# mic-preamp-stereo7.net
KiCad netlist of a schematic drawn in EAGLE
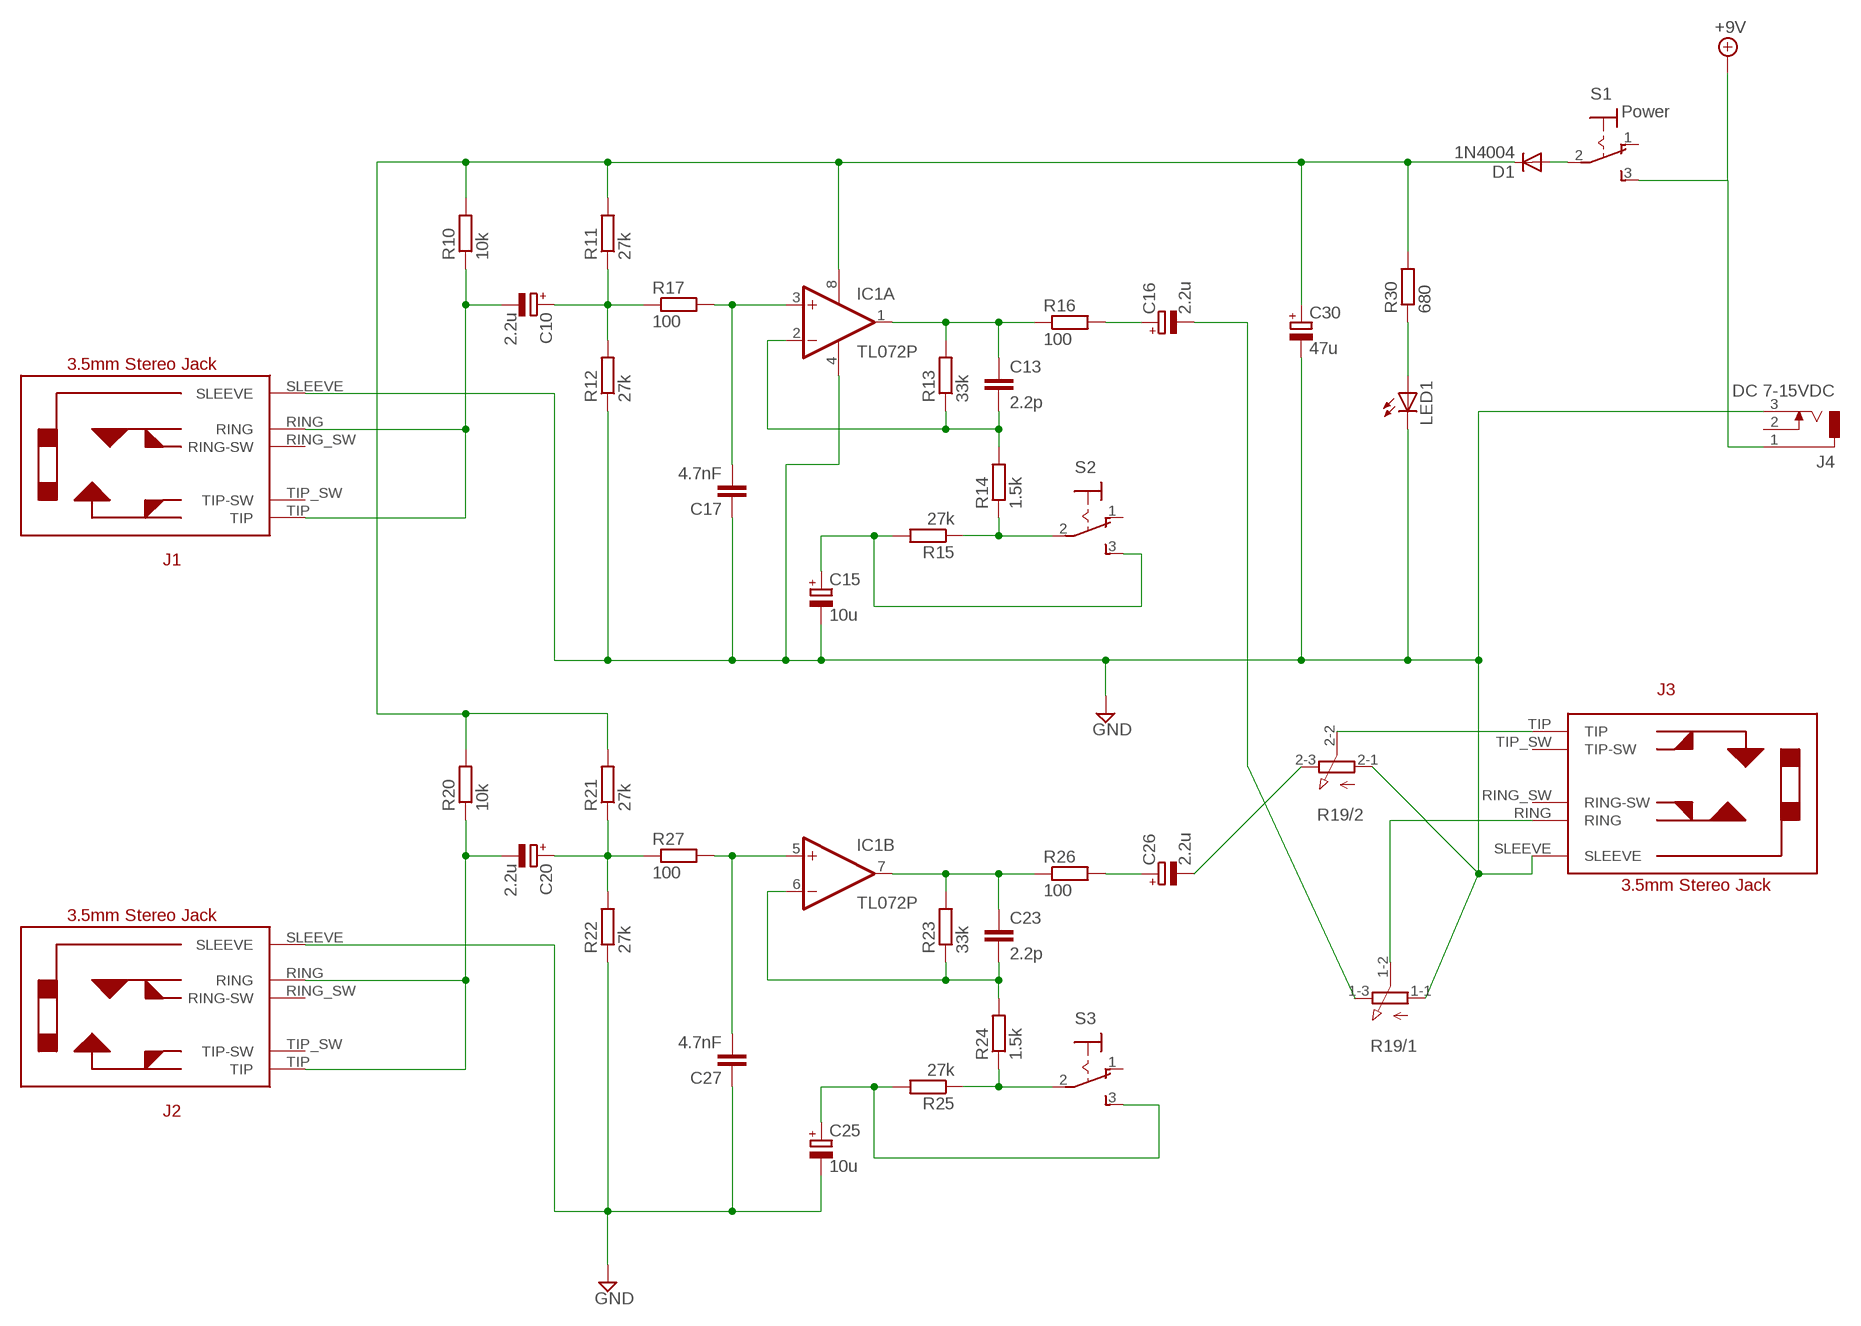
[diagram p0: schematic, sheet 1]

(export (version "E")
  (design (tool "Eeschema 10.0.6"))
  (components
    (comp (ref "C10")
      (value "2.2u")
      (footprint "eagle-import:E2-5")
      (libsource (lib "eagle-import") (part "CPOL-EUE2-5"))
    )
    (comp (ref "C13")
      (value "2.2p")
      (footprint "eagle-import:C025-024X044")
      (libsource (lib "eagle-import") (part "C-EU025-024X044"))
    )
    (comp (ref "C15")
      (value "10u")
      (footprint "eagle-import:E2-5")
      (libsource (lib "eagle-import") (part "CPOL-EUE2-5"))
    )
    (comp (ref "C16")
      (value "2.2u")
      (footprint "eagle-import:E2-5")
      (libsource (lib "eagle-import") (part "CPOL-EUE2-5"))
    )
    (comp (ref "C17")
      (value "4.7nF")
      (footprint "eagle-import:C025-024X044")
      (libsource (lib "eagle-import") (part "C-EU025-024X044"))
    )
    (comp (ref "C20")
      (value "2.2u")
      (footprint "eagle-import:E2-5")
      (libsource (lib "eagle-import") (part "CPOL-EUE2-5"))
    )
    (comp (ref "C23")
      (value "2.2p")
      (footprint "eagle-import:C025-024X044")
      (libsource (lib "eagle-import") (part "C-EU025-024X044"))
    )
    (comp (ref "C25")
      (value "10u")
      (footprint "eagle-import:E2-5")
      (libsource (lib "eagle-import") (part "CPOL-EUE2-5"))
    )
    (comp (ref "C26")
      (value "2.2u")
      (footprint "eagle-import:E2-5")
      (libsource (lib "eagle-import") (part "CPOL-EUE2-5"))
    )
    (comp (ref "C27")
      (value "4.7nF")
      (footprint "eagle-import:C025-024X044")
      (libsource (lib "eagle-import") (part "C-EU025-024X044"))
    )
    (comp (ref "C30")
      (value "47u")
      (footprint "eagle-import:E2-5")
      (libsource (lib "eagle-import") (part "CPOL-EUE2-5"))
    )
    (comp (ref "D1")
      (value "1N4004")
      (footprint "eagle-import:DO41-10")
      (libsource (lib "eagle-import") (part "1N4004"))
    )
    (comp (ref "IC1")
      (value "TL072P")
      (footprint "eagle-import:DIL08")
      (libsource (lib "eagle-import") (part "TL072P"))
    )
    (comp (ref "J1")
      (value "PICAXE_STEREOJACKSOCKET")
      (footprint "eagle-import:PICAXE_STEREOJACKSOCKET")
      (libsource (lib "eagle-import") (part "PICAXE_STEREOJACKSOCKET"))
    )
    (comp (ref "J2")
      (value "PICAXE_STEREOJACKSOCKET")
      (footprint "eagle-import:PICAXE_STEREOJACKSOCKET")
      (libsource (lib "eagle-import") (part "PICAXE_STEREOJACKSOCKET"))
    )
    (comp (ref "J3")
      (value "Stereo Out")
      (footprint "eagle-import:PICAXE_STEREOJACKSOCKET")
      (libsource (lib "eagle-import") (part "PICAXE_STEREOJACKSOCKET"))
    )
    (comp (ref "J4")
      (value "DC 7-15VDC")
      (footprint "eagle-import:DCJ0202")
      (libsource (lib "eagle-import") (part "DCJ0202"))
    )
    (comp (ref "LED1")
      (value "LED5MM")
      (footprint "eagle-import:LED5MM")
      (libsource (lib "eagle-import") (part "LED5MM"))
    )
    (comp (ref "R10")
      (value "10k")
      (footprint "eagle-import:0207_5V")
      (libsource (lib "eagle-import") (part "R-EU_0207/5V"))
    )
    (comp (ref "R11")
      (value "27k")
      (footprint "eagle-import:0207_5V")
      (libsource (lib "eagle-import") (part "R-EU_0207/5V"))
    )
    (comp (ref "R12")
      (value "27k")
      (footprint "eagle-import:0207_5V")
      (libsource (lib "eagle-import") (part "R-EU_0207/5V"))
    )
    (comp (ref "R13")
      (value "33k")
      (footprint "eagle-import:0207_5V")
      (libsource (lib "eagle-import") (part "R-EU_0207/5V"))
    )
    (comp (ref "R14")
      (value "1.5k")
      (footprint "eagle-import:0207_5V")
      (libsource (lib "eagle-import") (part "R-EU_0207/5V"))
    )
    (comp (ref "R15")
      (value "27k")
      (footprint "eagle-import:0207_5V")
      (libsource (lib "eagle-import") (part "R-EU_0207/5V"))
    )
    (comp (ref "R16")
      (value "100")
      (footprint "eagle-import:0207_5V")
      (libsource (lib "eagle-import") (part "R-EU_0207/5V"))
    )
    (comp (ref "R17")
      (value "100")
      (footprint "eagle-import:0207_5V")
      (libsource (lib "eagle-import") (part "resistor_R-EU_0207/5V"))
    )
    (comp (ref "R19")
      (value "3RP/1610G")
      (footprint "eagle-import:3RP_1610G")
      (libsource (lib "eagle-import") (part "3RP/1610G"))
    )
    (comp (ref "R20")
      (value "10k")
      (footprint "eagle-import:0207_5V")
      (libsource (lib "eagle-import") (part "R-EU_0207/5V"))
    )
    (comp (ref "R21")
      (value "27k")
      (footprint "eagle-import:0207_5V")
      (libsource (lib "eagle-import") (part "R-EU_0207/5V"))
    )
    (comp (ref "R22")
      (value "27k")
      (footprint "eagle-import:0207_5V")
      (libsource (lib "eagle-import") (part "R-EU_0207/5V"))
    )
    (comp (ref "R23")
      (value "33k")
      (footprint "eagle-import:0207_5V")
      (libsource (lib "eagle-import") (part "R-EU_0207/5V"))
    )
    (comp (ref "R24")
      (value "1.5k")
      (footprint "eagle-import:0207_5V")
      (libsource (lib "eagle-import") (part "R-EU_0207/5V"))
    )
    (comp (ref "R25")
      (value "27k")
      (footprint "eagle-import:0207_5V")
      (libsource (lib "eagle-import") (part "R-EU_0207/5V"))
    )
    (comp (ref "R26")
      (value "100")
      (footprint "eagle-import:0207_5V")
      (libsource (lib "eagle-import") (part "R-EU_0207/5V"))
    )
    (comp (ref "R27")
      (value "100")
      (footprint "eagle-import:0207_5V")
      (libsource (lib "eagle-import") (part "resistor_R-EU_0207/5V"))
    )
    (comp (ref "R30")
      (value "680")
      (footprint "eagle-import:0207_5V")
      (libsource (lib "eagle-import") (part "R-EU_0207/5V"))
    )
    (comp (ref "S1")
      (value "Power")
      (footprint "eagle-import:M9040P")
      (libsource (lib "eagle-import") (part "M9040P"))
    )
    (comp (ref "S2")
      (value "M9040P")
      (footprint "eagle-import:M9040P")
      (libsource (lib "eagle-import") (part "M9040P"))
    )
    (comp (ref "S3")
      (value "M9040P")
      (footprint "eagle-import:M9040P")
      (libsource (lib "eagle-import") (part "M9040P"))
    )
  )
  (nets
    (net (code "1") (name "+9V") (class "Default")
      (node (ref "J4") (pin "1") (pinfunction "1_1") (pintype "passive"))
      (node (ref "S1") (pin "3") (pinfunction "S_3") (pintype "passive"))
    )
    (net (code "2") (name "GND") (class "Default")
      (node (ref "C15") (pin "-") (pinfunction "-_-") (pintype "passive"))
      (node (ref "C17") (pin "1") (pinfunction "1_1") (pintype "passive"))
      (node (ref "C25") (pin "-") (pinfunction "-_-") (pintype "passive"))
      (node (ref "C27") (pin "1") (pinfunction "1_1") (pintype "passive"))
      (node (ref "C30") (pin "-") (pinfunction "-_-") (pintype "passive"))
      (node (ref "IC1") (pin "4") (pinfunction "V-_4") (pintype "power_in"))
      (node (ref "J1") (pin "SLEEVE") (pinfunction "SLEEVE_SLEEVE") (pintype "bidirectional"))
      (node (ref "J2") (pin "SLEEVE") (pinfunction "SLEEVE_SLEEVE") (pintype "bidirectional"))
      (node (ref "J3") (pin "SLEEVE") (pinfunction "SLEEVE_SLEEVE") (pintype "bidirectional"))
      (node (ref "J4") (pin "3") (pinfunction "3_3") (pintype "passive"))
      (node (ref "LED1") (pin "K") (pinfunction "C_K") (pintype "passive"))
      (node (ref "R12") (pin "1") (pinfunction "1_1") (pintype "passive"))
      (node (ref "R19") (pin "1-1") (pinfunction "A_1-1") (pintype "passive"))
      (node (ref "R19") (pin "2-1") (pinfunction "A_2-1") (pintype "passive"))
      (node (ref "R22") (pin "1") (pinfunction "1_1") (pintype "passive"))
    )
    (net (code "3") (name "Net-(C10-Pad+)") (class "Default")
      (node (ref "C10") (pin "+") (pinfunction "+_+") (pintype "passive"))
      (node (ref "R11") (pin "1") (pinfunction "1_1") (pintype "passive"))
      (node (ref "R12") (pin "2") (pinfunction "2_2") (pintype "passive"))
      (node (ref "R17") (pin "1") (pinfunction "1_1") (pintype "passive"))
    )
    (net (code "4") (name "Net-(C10-Pad-)") (class "Default")
      (node (ref "C10") (pin "-") (pinfunction "-_-") (pintype "passive"))
      (node (ref "J1") (pin "RING") (pinfunction "RING_RING") (pintype "bidirectional"))
      (node (ref "J1") (pin "TIP") (pinfunction "TIP_TIP") (pintype "bidirectional"))
      (node (ref "R10") (pin "1") (pinfunction "1_1") (pintype "passive"))
    )
    (net (code "5") (name "Net-(C16-Pad+)") (class "Default")
      (node (ref "C16") (pin "+") (pinfunction "+_+") (pintype "passive"))
      (node (ref "R16") (pin "2") (pinfunction "2_2") (pintype "passive"))
    )
    (net (code "6") (name "Net-(C20-Pad+)") (class "Default")
      (node (ref "C20") (pin "+") (pinfunction "+_+") (pintype "passive"))
      (node (ref "R21") (pin "1") (pinfunction "1_1") (pintype "passive"))
      (node (ref "R22") (pin "2") (pinfunction "2_2") (pintype "passive"))
      (node (ref "R27") (pin "1") (pinfunction "1_1") (pintype "passive"))
    )
    (net (code "7") (name "Net-(C20-Pad-)") (class "Default")
      (node (ref "C20") (pin "-") (pinfunction "-_-") (pintype "passive"))
      (node (ref "J2") (pin "RING") (pinfunction "RING_RING") (pintype "bidirectional"))
      (node (ref "J2") (pin "TIP") (pinfunction "TIP_TIP") (pintype "bidirectional"))
      (node (ref "R20") (pin "1") (pinfunction "1_1") (pintype "passive"))
    )
    (net (code "8") (name "Net-(C26-Pad+)") (class "Default")
      (node (ref "C26") (pin "+") (pinfunction "+_+") (pintype "passive"))
      (node (ref "R26") (pin "2") (pinfunction "2_2") (pintype "passive"))
    )
    (net (code "9") (name "Net-(IC1A-+IN)") (class "Default")
      (node (ref "C17") (pin "2") (pinfunction "2_2") (pintype "passive"))
      (node (ref "IC1") (pin "3") (pinfunction "+IN_3") (pintype "input"))
      (node (ref "R17") (pin "2") (pinfunction "2_2") (pintype "passive"))
    )
    (net (code "10") (name "Net-(IC1A--IN)") (class "Default")
      (node (ref "C13") (pin "2") (pinfunction "2_2") (pintype "passive"))
      (node (ref "IC1") (pin "2") (pinfunction "-IN_2") (pintype "input"))
      (node (ref "R13") (pin "1") (pinfunction "1_1") (pintype "passive"))
      (node (ref "R14") (pin "2") (pinfunction "2_2") (pintype "passive"))
    )
    (net (code "11") (name "Net-(IC1A-OUT)") (class "Default")
      (node (ref "C13") (pin "1") (pinfunction "1_1") (pintype "passive"))
      (node (ref "IC1") (pin "1") (pinfunction "OUT_1") (pintype "output"))
      (node (ref "R13") (pin "2") (pinfunction "2_2") (pintype "passive"))
      (node (ref "R16") (pin "1") (pinfunction "1_1") (pintype "passive"))
    )
    (net (code "12") (name "Net-(IC1B-+IN)") (class "Default")
      (node (ref "C27") (pin "2") (pinfunction "2_2") (pintype "passive"))
      (node (ref "IC1") (pin "5") (pinfunction "+IN_5") (pintype "input"))
      (node (ref "R27") (pin "2") (pinfunction "2_2") (pintype "passive"))
    )
    (net (code "13") (name "Net-(IC1B--IN)") (class "Default")
      (node (ref "C23") (pin "2") (pinfunction "2_2") (pintype "passive"))
      (node (ref "IC1") (pin "6") (pinfunction "-IN_6") (pintype "input"))
      (node (ref "R23") (pin "1") (pinfunction "1_1") (pintype "passive"))
      (node (ref "R24") (pin "2") (pinfunction "2_2") (pintype "passive"))
    )
    (net (code "14") (name "Net-(IC1B-OUT)") (class "Default")
      (node (ref "C23") (pin "1") (pinfunction "1_1") (pintype "passive"))
      (node (ref "IC1") (pin "7") (pinfunction "OUT_7") (pintype "output"))
      (node (ref "R23") (pin "2") (pinfunction "2_2") (pintype "passive"))
      (node (ref "R26") (pin "1") (pinfunction "1_1") (pintype "passive"))
    )
    (net (code "15") (name "Net-(IC1C-V+)") (class "Default")
      (node (ref "C30") (pin "+") (pinfunction "+_+") (pintype "passive"))
      (node (ref "D1") (pin "C") (pinfunction "C_C") (pintype "passive"))
      (node (ref "IC1") (pin "8") (pinfunction "V+_8") (pintype "power_in"))
      (node (ref "R10") (pin "2") (pinfunction "2_2") (pintype "passive"))
      (node (ref "R11") (pin "2") (pinfunction "2_2") (pintype "passive"))
      (node (ref "R20") (pin "2") (pinfunction "2_2") (pintype "passive"))
      (node (ref "R21") (pin "2") (pinfunction "2_2") (pintype "passive"))
      (node (ref "R30") (pin "2") (pinfunction "2_2") (pintype "passive"))
    )
    (net (code "16") (name "Net-(LED1-PadA)") (class "Default")
      (node (ref "LED1") (pin "A") (pinfunction "A_A") (pintype "passive"))
      (node (ref "R30") (pin "1") (pinfunction "1_1") (pintype "passive"))
    )
    (net (code "17") (name "Net-(R19A-E)") (class "Default")
      (node (ref "C16") (pin "-") (pinfunction "-_-") (pintype "passive"))
      (node (ref "R19") (pin "1-3") (pinfunction "E_1-3") (pintype "passive"))
    )
    (net (code "18") (name "Net-(R19A-S)") (class "Default")
      (node (ref "J3") (pin "RING") (pinfunction "RING_RING") (pintype "bidirectional"))
      (node (ref "R19") (pin "1-2") (pinfunction "S_1-2") (pintype "passive"))
    )
    (net (code "19") (name "Net-(R19B-E)") (class "Default")
      (node (ref "C26") (pin "-") (pinfunction "-_-") (pintype "passive"))
      (node (ref "R19") (pin "2-3") (pinfunction "E_2-3") (pintype "passive"))
    )
    (net (code "20") (name "Net-(R19B-S)") (class "Default")
      (node (ref "J3") (pin "TIP") (pinfunction "TIP_TIP") (pintype "bidirectional"))
      (node (ref "R19") (pin "2-2") (pinfunction "S_2-2") (pintype "passive"))
    )
    (net (code "21") (name "Net-(S1-P)") (class "Default")
      (node (ref "D1") (pin "A") (pinfunction "A_A") (pintype "passive"))
      (node (ref "S1") (pin "2") (pinfunction "P_2") (pintype "passive"))
    )
    (net (code "22") (name "Net-(S2-P)") (class "Default")
      (node (ref "R14") (pin "1") (pinfunction "1_1") (pintype "passive"))
      (node (ref "R15") (pin "1") (pinfunction "1_1") (pintype "passive"))
      (node (ref "S2") (pin "2") (pinfunction "P_2") (pintype "passive"))
    )
    (net (code "23") (name "Net-(S2-S)") (class "Default")
      (node (ref "C15") (pin "+") (pinfunction "+_+") (pintype "passive"))
      (node (ref "R15") (pin "2") (pinfunction "2_2") (pintype "passive"))
      (node (ref "S2") (pin "3") (pinfunction "S_3") (pintype "passive"))
    )
    (net (code "24") (name "Net-(S3-P)") (class "Default")
      (node (ref "R24") (pin "1") (pinfunction "1_1") (pintype "passive"))
      (node (ref "R25") (pin "1") (pinfunction "1_1") (pintype "passive"))
      (node (ref "S3") (pin "2") (pinfunction "P_2") (pintype "passive"))
    )
    (net (code "25") (name "Net-(S3-S)") (class "Default")
      (node (ref "C25") (pin "+") (pinfunction "+_+") (pintype "passive"))
      (node (ref "R25") (pin "2") (pinfunction "2_2") (pintype "passive"))
      (node (ref "S3") (pin "3") (pinfunction "S_3") (pintype "passive"))
    )
    (net (code "26") (name "unconnected-(J1-RING-SW-PadRING_SW)") (class "Default")
      (node (ref "J1") (pin "RING_SW") (pinfunction "RING-SW_RING_SW") (pintype "bidirectional"))
    )
    (net (code "27") (name "unconnected-(J1-TIP-SW-PadTIP_SW)") (class "Default")
      (node (ref "J1") (pin "TIP_SW") (pinfunction "TIP-SW_TIP_SW") (pintype "bidirectional"))
    )
    (net (code "28") (name "unconnected-(J2-RING-SW-PadRING_SW)") (class "Default")
      (node (ref "J2") (pin "RING_SW") (pinfunction "RING-SW_RING_SW") (pintype "bidirectional"))
    )
    (net (code "29") (name "unconnected-(J2-TIP-SW-PadTIP_SW)") (class "Default")
      (node (ref "J2") (pin "TIP_SW") (pinfunction "TIP-SW_TIP_SW") (pintype "bidirectional"))
    )
    (net (code "30") (name "unconnected-(J3-RING-SW-PadRING_SW)") (class "Default")
      (node (ref "J3") (pin "RING_SW") (pinfunction "RING-SW_RING_SW") (pintype "bidirectional"))
    )
    (net (code "31") (name "unconnected-(J3-TIP-SW-PadTIP_SW)") (class "Default")
      (node (ref "J3") (pin "TIP_SW") (pinfunction "TIP-SW_TIP_SW") (pintype "bidirectional"))
    )
    (net (code "32") (name "unconnected-(J4-Pad2)") (class "Default")
      (node (ref "J4") (pin "2") (pinfunction "2_2") (pintype "passive"))
    )
    (net (code "33") (name "unconnected-(S1-O-Pad1)") (class "Default")
      (node (ref "S1") (pin "1") (pinfunction "O_1") (pintype "passive"))
    )
    (net (code "34") (name "unconnected-(S2-O-Pad1)") (class "Default")
      (node (ref "S2") (pin "1") (pinfunction "O_1") (pintype "passive"))
    )
    (net (code "35") (name "unconnected-(S3-O-Pad1)") (class "Default")
      (node (ref "S3") (pin "1") (pinfunction "O_1") (pintype "passive"))
    )
  )
)
